# Qwiic_Adaptive_Switch_Input.net
KiCad netlist of a schematic drawn in EAGLE
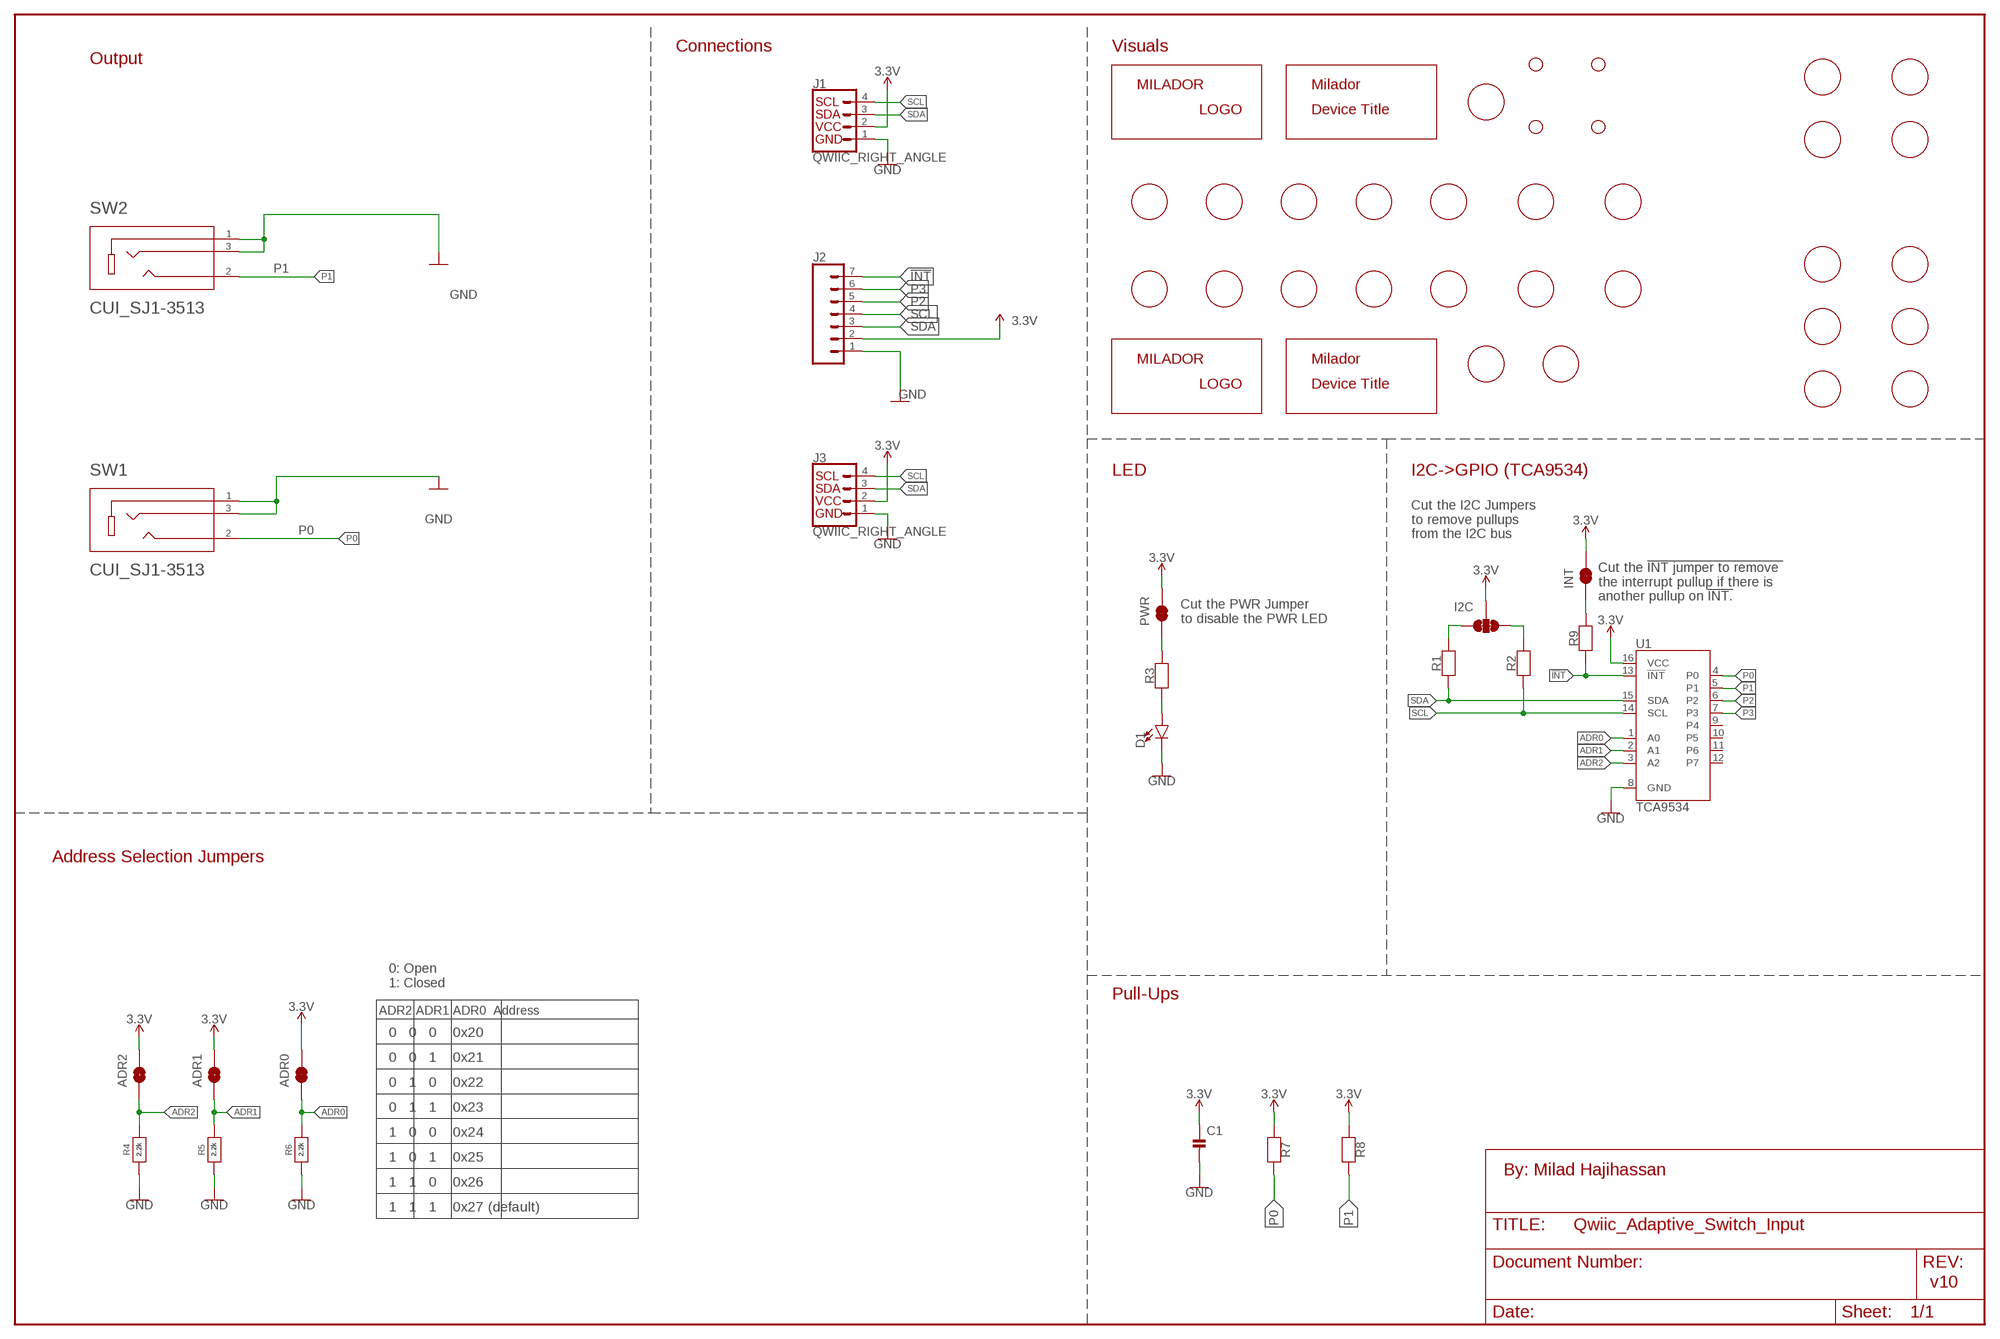
[diagram p0: schematic, sheet 1]

(export (version "E")
  (design (tool "Eeschema 10.0.6"))
  (components
    (comp (ref "ADR0")
      (value "JUMPERS-SMT_2_NC_TRACE_SILK")
      (footprint "eagle-import:JUMPERS_SMT-JUMPER_2_NC_TRACE_SILK")
      (libsource (lib "eagle-import") (part "JUMPERS-SMT_2_NC_TRACE_SILK"))
    )
    (comp (ref "ADR1")
      (value "JUMPERS-SMT_2_NC_TRACE_SILK")
      (footprint "eagle-import:JUMPERS_SMT-JUMPER_2_NC_TRACE_SILK")
      (libsource (lib "eagle-import") (part "JUMPERS-SMT_2_NC_TRACE_SILK"))
    )
    (comp (ref "ADR2")
      (value "JUMPERS-SMT_2_NC_TRACE_SILK")
      (footprint "eagle-import:JUMPERS_SMT-JUMPER_2_NC_TRACE_SILK")
      (libsource (lib "eagle-import") (part "JUMPERS-SMT_2_NC_TRACE_SILK"))
    )
    (comp (ref "C1")
      (value "0.1uF")
      (footprint "eagle-import:0805-MP")
      (libsource (lib "eagle-import") (part "CAP_CERAMIC-0805-MP"))
    )
    (comp (ref "D1")
      (value "RED")
      (footprint "eagle-import:CHIPLED_0805_NOOUTLINE")
      (libsource (lib "eagle-import") (part "LED0805_NOOUTLINE"))
    )
    (comp (ref "H1")
      (value "STAND-OFF-3.3")
      (footprint "eagle-import:STAND-OFF-3.3")
      (libsource (lib "eagle-import") (part "STAND-OFF-3.3"))
    )
    (comp (ref "H2")
      (value "STAND-OFF-3.3")
      (footprint "eagle-import:STAND-OFF-3.3")
      (libsource (lib "eagle-import") (part "STAND-OFF-3.3"))
    )
    (comp (ref "H3")
      (value "STAND-OFF-3.3")
      (footprint "eagle-import:STAND-OFF-3.3")
      (libsource (lib "eagle-import") (part "STAND-OFF-3.3"))
    )
    (comp (ref "H4")
      (value "STAND-OFF-3.3")
      (footprint "eagle-import:STAND-OFF-3.3")
      (libsource (lib "eagle-import") (part "STAND-OFF-3.3"))
    )
    (comp (ref "I2C")
      (value "JUMPERS_JUMPER-SMT_3_2-NC_TRACE_SILK")
      (footprint "eagle-import:JUMPERS_SMT-JUMPER_3_2-NC_TRACE_SILK")
      (libsource (lib "eagle-import") (part "JUMPERS_JUMPER-SMT_3_2-NC_TRACE_SILK"))
    )
    (comp (ref "INT")
      (value "JUMPERS-SMT_2_NC_TRACE_SILK")
      (footprint "eagle-import:JUMPERS_SMT-JUMPER_2_NC_TRACE_SILK")
      (libsource (lib "eagle-import") (part "JUMPERS-SMT_2_NC_TRACE_SILK"))
    )
    (comp (ref "J1")
      (value "QWIIC_RIGHT_ANGLE")
      (footprint "eagle-import:CONNECTORS_JST04_1MM_RA")
      (fields (field (name "PROD_ID") "CONN-13694"))
      (libsource (lib "eagle-import") (part "QWIIC_CONNECTORSJS-1MM"))
    )
    (comp (ref "J2")
      (value "CONNECTORS_CONN_071X07_NO_SILK")
      (footprint "eagle-import:CONNECTORS_1X07_NO_SILK")
      (libsource (lib "eagle-import") (part "CONNECTORS_CONN_071X07_NO_SILK"))
    )
    (comp (ref "J3")
      (value "QWIIC_RIGHT_ANGLE")
      (footprint "eagle-import:CONNECTORS_JST04_1MM_RA")
      (fields (field (name "PROD_ID") "CONN-13694"))
      (libsource (lib "eagle-import") (part "QWIIC_CONNECTORSJS-1MM"))
    )
    (comp (ref "LABEL_!INT_BOTTOM")
      (value "MILADOR-LABEL-!INT")
      (footprint "eagle-import:LABEL-!INT")
      (libsource (lib "eagle-import") (part "MILADOR-LABEL-!INT"))
    )
    (comp (ref "LABEL_!INT_TOP")
      (value "MILADOR-LABEL-!INT")
      (footprint "eagle-import:LABEL-!INT")
      (libsource (lib "eagle-import") (part "MILADOR-LABEL-!INT"))
    )
    (comp (ref "LABEL_3V_BOTTOM")
      (value "MILADOR-LABEL-3V")
      (footprint "eagle-import:LABEL-3V")
      (libsource (lib "eagle-import") (part "MILADOR-LABEL-3V"))
    )
    (comp (ref "LABEL_3V_TOP")
      (value "MILADOR-LABEL-3V")
      (footprint "eagle-import:LABEL-3V")
      (libsource (lib "eagle-import") (part "MILADOR-LABEL-3V"))
    )
    (comp (ref "LABEL_ADR0")
      (value "MILADOR-LABEL-ADR0")
      (footprint "eagle-import:LABEL-ADR0")
      (libsource (lib "eagle-import") (part "MILADOR-LABEL-ADR0"))
    )
    (comp (ref "LABEL_ADR1")
      (value "MILADOR-LABEL-ADR1")
      (footprint "eagle-import:LABEL-ADR1")
      (libsource (lib "eagle-import") (part "MILADOR-LABEL-ADR1"))
    )
    (comp (ref "LABEL_ADR2")
      (value "MILADOR-LABEL-ADR2")
      (footprint "eagle-import:LABEL-ADR2")
      (libsource (lib "eagle-import") (part "MILADOR-LABEL-ADR2"))
    )
    (comp (ref "LABEL_GND_BOTTOM")
      (value "MILADOR-LABEL-GND")
      (footprint "eagle-import:LABEL-GND")
      (libsource (lib "eagle-import") (part "MILADOR-LABEL-GND"))
    )
    (comp (ref "LABEL_GND_TOP")
      (value "MILADOR-LABEL-GND")
      (footprint "eagle-import:LABEL-GND")
      (libsource (lib "eagle-import") (part "MILADOR-LABEL-GND"))
    )
    (comp (ref "LABEL_I2C")
      (value "MILADOR-LABEL-I2C")
      (footprint "eagle-import:LABEL-I2C")
      (libsource (lib "eagle-import") (part "MILADOR-LABEL-I2C"))
    )
    (comp (ref "LABEL_I2C_ADDRESS")
      (value "MILADOR-LABEL-ADDRESS-0X27")
      (footprint "eagle-import:LABEL-ADDRESS-27")
      (libsource (lib "eagle-import") (part "MILADOR-LABEL-ADDRESS-0X27"))
    )
    (comp (ref "LABEL_INPUT_BOTTOM")
      (value "MILADOR-SWITCH-NAME-SW-INPUT")
      (footprint "eagle-import:SWITCH-INPUT")
      (libsource (lib "eagle-import") (part "MILADOR-SWITCH-NAME-SW-INPUT"))
    )
    (comp (ref "LABEL_INPUT_TOP")
      (value "MILADOR-SWITCH-NAME-SW-INPUT")
      (footprint "eagle-import:SWITCH-INPUT")
      (libsource (lib "eagle-import") (part "MILADOR-SWITCH-NAME-SW-INPUT"))
    )
    (comp (ref "LABEL_INT")
      (value "MILADOR-LABEL-INT")
      (footprint "eagle-import:LABEL-INT")
      (libsource (lib "eagle-import") (part "MILADOR-LABEL-INT"))
    )
    (comp (ref "LABEL_MILADOR_BOTTOM")
      (value "MILADOR-LOGO-")
      (footprint "eagle-import:MILADOR_LOGO1")
      (libsource (lib "eagle-import") (part "MILADOR-LOGO-"))
    )
    (comp (ref "LABEL_MILADOR_TOP")
      (value "MILADOR-LOGO-")
      (footprint "eagle-import:MILADOR_LOGO1")
      (libsource (lib "eagle-import") (part "MILADOR-LOGO-"))
    )
    (comp (ref "LABEL_P0_BOTTOM")
      (value "MILADOR-LABEL-P0")
      (footprint "eagle-import:LABEL-P0")
      (libsource (lib "eagle-import") (part "MILADOR-LABEL-P0"))
    )
    (comp (ref "LABEL_P1_BOTTOM")
      (value "MILADOR-LABEL-P1")
      (footprint "eagle-import:LABEL-P1")
      (libsource (lib "eagle-import") (part "MILADOR-LABEL-P1"))
    )
    (comp (ref "LABEL_P2_BOTTOM")
      (value "MILADOR-LABEL-P2")
      (footprint "eagle-import:LABEL-P2")
      (libsource (lib "eagle-import") (part "MILADOR-LABEL-P2"))
    )
    (comp (ref "LABEL_P2_TOP")
      (value "MILADOR-LABEL-P2")
      (footprint "eagle-import:LABEL-P2")
      (libsource (lib "eagle-import") (part "MILADOR-LABEL-P2"))
    )
    (comp (ref "LABEL_P3_BOTTOM")
      (value "MILADOR-LABEL-P3")
      (footprint "eagle-import:LABEL-P3")
      (libsource (lib "eagle-import") (part "MILADOR-LABEL-P3"))
    )
    (comp (ref "LABEL_P3_TOP")
      (value "MILADOR-LABEL-P3")
      (footprint "eagle-import:LABEL-P3")
      (libsource (lib "eagle-import") (part "MILADOR-LABEL-P3"))
    )
    (comp (ref "LABEL_PWR")
      (value "MILADOR-LABEL-PWR")
      (footprint "eagle-import:LABEL-PWR")
      (libsource (lib "eagle-import") (part "MILADOR-LABEL-PWR"))
    )
    (comp (ref "LABEL_SW1")
      (value "MILADOR-SWITCH-NAME-SW1")
      (footprint "eagle-import:SWITCH-SW1")
      (libsource (lib "eagle-import") (part "MILADOR-SWITCH-NAME-SW1"))
    )
    (comp (ref "LABEL_SW2")
      (value "MILADOR-SWITCH-NAME-SW2")
      (footprint "eagle-import:SWITCH-SW2")
      (libsource (lib "eagle-import") (part "MILADOR-SWITCH-NAME-SW2"))
    )
    (comp (ref "LABEL_TITLE_BOTTOM")
      (value "MILADOR-DEVICE-QWIIC-SWITCH")
      (footprint "eagle-import:MILADOR_QWIIC_SWITCH")
      (libsource (lib "eagle-import") (part "MILADOR-DEVICE-QWIIC-SWITCH"))
    )
    (comp (ref "LABEL_TITLE_TOP")
      (value "MILADOR-DEVICE-QWIIC-SWITCH-SM")
      (footprint "eagle-import:MILADOR_QWIIC_SWITCH_SM")
      (libsource (lib "eagle-import") (part "MILADOR-DEVICE-QWIIC-SWITCH-SM"))
    )
    (comp (ref "LABE_SCL_BOTTOM")
      (value "MILADOR-LABEL-SCL")
      (footprint "eagle-import:LABEL-SCL")
      (libsource (lib "eagle-import") (part "MILADOR-LABEL-SCL"))
    )
    (comp (ref "LABE_SCL_TOP")
      (value "MILADOR-LABEL-SCL")
      (footprint "eagle-import:LABEL-SCL")
      (libsource (lib "eagle-import") (part "MILADOR-LABEL-SCL"))
    )
    (comp (ref "LABE_SDA_BOTTOM")
      (value "MILADOR-LABEL-SDA")
      (footprint "eagle-import:LABEL-SDA")
      (libsource (lib "eagle-import") (part "MILADOR-LABEL-SDA"))
    )
    (comp (ref "LABE_SDA_TOP")
      (value "MILADOR-LABEL-SDA")
      (footprint "eagle-import:LABEL-SDA")
      (libsource (lib "eagle-import") (part "MILADOR-LABEL-SDA"))
    )
    (comp (ref "PWR")
      (value "JUMPERS-SMT_2_NC_TRACE_SILK")
      (footprint "eagle-import:JUMPERS_SMT-JUMPER_2_NC_TRACE_SILK")
      (libsource (lib "eagle-import") (part "JUMPERS-SMT_2_NC_TRACE_SILK"))
    )
    (comp (ref "R1")
      (value "2.2k")
      (footprint "eagle-import:0805-MP")
      (libsource (lib "eagle-import") (part "RESISTOR-0805-MP"))
    )
    (comp (ref "R2")
      (value "2.2k")
      (footprint "eagle-import:0805-MP")
      (libsource (lib "eagle-import") (part "RESISTOR-0805-MP"))
    )
    (comp (ref "R3")
      (value "1k")
      (footprint "eagle-import:0805-MP")
      (libsource (lib "eagle-import") (part "RESISTOR-0805-MP"))
    )
    (comp (ref "R4")
      (value "2.2k")
      (footprint "eagle-import:0805-MP")
      (libsource (lib "eagle-import") (part "RESISTOR-0805-MP"))
    )
    (comp (ref "R5")
      (value "2.2k")
      (footprint "eagle-import:0805-MP")
      (libsource (lib "eagle-import") (part "RESISTOR-0805-MP"))
    )
    (comp (ref "R6")
      (value "2.2k")
      (footprint "eagle-import:0805-MP")
      (libsource (lib "eagle-import") (part "RESISTOR-0805-MP"))
    )
    (comp (ref "R7")
      (value "4.7K")
      (footprint "eagle-import:0805-MP")
      (libsource (lib "eagle-import") (part "RESISTOR-0805-MP"))
    )
    (comp (ref "R8")
      (value "4.7K")
      (footprint "eagle-import:0805-MP")
      (libsource (lib "eagle-import") (part "RESISTOR-0805-MP"))
    )
    (comp (ref "R9")
      (value "10k")
      (footprint "eagle-import:0805-MP")
      (libsource (lib "eagle-import") (part "RESISTOR-0805-MP"))
    )
    (comp (ref "SW1")
      (value "CUI_SJ1-3513")
      (footprint "eagle-import:CUI_SJ1-3513")
      (libsource (lib "eagle-import") (part "CUI_SJ1-3513"))
    )
    (comp (ref "SW2")
      (value "CUI_SJ1-3513")
      (footprint "eagle-import:CUI_SJ1-3513")
      (libsource (lib "eagle-import") (part "CUI_SJ1-3513"))
    )
    (comp (ref "U1")
      (value "TCA9534")
      (footprint "eagle-import:16SOIC")
      (libsource (lib "eagle-import") (part "TCA9534DWR"))
    )
  )
  (nets
    (net (code "1") (name "/~{INT}") (class "Default")
      (node (ref "J2") (pin "7") (pinfunction "7_7") (pintype "passive"))
      (node (ref "R9") (pin "1") (pinfunction "1_1") (pintype "passive"))
      (node (ref "U1") (pin "13") (pinfunction "~{INT}_13") (pintype "bidirectional"))
    )
    (net (code "2") (name "3.3V") (class "Default")
      (node (ref "ADR0") (pin "2") (pinfunction "2_2") (pintype "passive"))
      (node (ref "ADR1") (pin "2") (pinfunction "2_2") (pintype "passive"))
      (node (ref "ADR2") (pin "2") (pinfunction "2_2") (pintype "passive"))
      (node (ref "C1") (pin "1") (pinfunction "1_1") (pintype "passive"))
      (node (ref "I2C") (pin "2") (pinfunction "2_2") (pintype "passive"))
      (node (ref "INT") (pin "2") (pinfunction "2_2") (pintype "passive"))
      (node (ref "J1") (pin "2") (pinfunction "2_2") (pintype "power_in"))
      (node (ref "J2") (pin "2") (pinfunction "2_2") (pintype "passive"))
      (node (ref "J3") (pin "2") (pinfunction "2_2") (pintype "power_in"))
      (node (ref "PWR") (pin "2") (pinfunction "2_2") (pintype "passive"))
      (node (ref "R7") (pin "1") (pinfunction "1_1") (pintype "passive"))
      (node (ref "R8") (pin "1") (pinfunction "1_1") (pintype "passive"))
      (node (ref "U1") (pin "16") (pinfunction "VCC_16") (pintype "bidirectional"))
    )
    (net (code "3") (name "ADR0") (class "Default")
      (node (ref "ADR0") (pin "1") (pinfunction "1_1") (pintype "passive"))
      (node (ref "R6") (pin "2") (pinfunction "2_2") (pintype "passive"))
      (node (ref "U1") (pin "1") (pinfunction "A0_1") (pintype "bidirectional"))
    )
    (net (code "4") (name "ADR1") (class "Default")
      (node (ref "ADR1") (pin "1") (pinfunction "1_1") (pintype "passive"))
      (node (ref "R5") (pin "2") (pinfunction "2_2") (pintype "passive"))
      (node (ref "U1") (pin "2") (pinfunction "A1_2") (pintype "bidirectional"))
    )
    (net (code "5") (name "ADR2") (class "Default")
      (node (ref "ADR2") (pin "1") (pinfunction "1_1") (pintype "passive"))
      (node (ref "R4") (pin "2") (pinfunction "2_2") (pintype "passive"))
      (node (ref "U1") (pin "3") (pinfunction "A2_3") (pintype "bidirectional"))
    )
    (net (code "6") (name "GND") (class "Default")
      (node (ref "C1") (pin "2") (pinfunction "2_2") (pintype "passive"))
      (node (ref "D1") (pin "C") (pinfunction "C_C") (pintype "passive"))
      (node (ref "J1") (pin "1") (pinfunction "1_1") (pintype "power_in"))
      (node (ref "J2") (pin "1") (pinfunction "1_1") (pintype "passive"))
      (node (ref "J3") (pin "1") (pinfunction "1_1") (pintype "power_in"))
      (node (ref "R4") (pin "1") (pinfunction "1_1") (pintype "passive"))
      (node (ref "R5") (pin "1") (pinfunction "1_1") (pintype "passive"))
      (node (ref "R6") (pin "1") (pinfunction "1_1") (pintype "passive"))
      (node (ref "SW1") (pin "1") (pinfunction "1_1") (pintype "passive"))
      (node (ref "SW1") (pin "3") (pinfunction "3_3") (pintype "passive"))
      (node (ref "SW2") (pin "1") (pinfunction "1_1") (pintype "passive"))
      (node (ref "SW2") (pin "3") (pinfunction "3_3") (pintype "passive"))
      (node (ref "U1") (pin "8") (pinfunction "GND_8") (pintype "bidirectional"))
    )
    (net (code "7") (name "Net-(D1-PadA)") (class "Default")
      (node (ref "D1") (pin "A") (pinfunction "A_A") (pintype "passive"))
      (node (ref "R3") (pin "1") (pinfunction "1_1") (pintype "passive"))
    )
    (net (code "8") (name "Net-(I2C-Pad1)") (class "Default")
      (node (ref "I2C") (pin "1") (pinfunction "1_1") (pintype "passive"))
      (node (ref "R1") (pin "2") (pinfunction "2_2") (pintype "passive"))
    )
    (net (code "9") (name "Net-(I2C-Pad3)") (class "Default")
      (node (ref "I2C") (pin "3") (pinfunction "3_3") (pintype "passive"))
      (node (ref "R2") (pin "2") (pinfunction "2_2") (pintype "passive"))
    )
    (net (code "10") (name "Net-(INT-Pad1)") (class "Default")
      (node (ref "INT") (pin "1") (pinfunction "1_1") (pintype "passive"))
      (node (ref "R9") (pin "2") (pinfunction "2_2") (pintype "passive"))
    )
    (net (code "11") (name "Net-(PWR-Pad1)") (class "Default")
      (node (ref "PWR") (pin "1") (pinfunction "1_1") (pintype "passive"))
      (node (ref "R3") (pin "2") (pinfunction "2_2") (pintype "passive"))
    )
    (net (code "12") (name "P0") (class "Default")
      (node (ref "R7") (pin "2") (pinfunction "2_2") (pintype "passive"))
      (node (ref "SW1") (pin "2") (pinfunction "2_2") (pintype "passive"))
      (node (ref "U1") (pin "4") (pinfunction "P0_4") (pintype "bidirectional"))
    )
    (net (code "13") (name "P1") (class "Default")
      (node (ref "R8") (pin "2") (pinfunction "2_2") (pintype "passive"))
      (node (ref "SW2") (pin "2") (pinfunction "2_2") (pintype "passive"))
      (node (ref "U1") (pin "5") (pinfunction "P1_5") (pintype "bidirectional"))
    )
    (net (code "14") (name "P2") (class "Default")
      (node (ref "J2") (pin "5") (pinfunction "5_5") (pintype "passive"))
      (node (ref "U1") (pin "6") (pinfunction "P2_6") (pintype "bidirectional"))
    )
    (net (code "15") (name "P3") (class "Default")
      (node (ref "J2") (pin "6") (pinfunction "6_6") (pintype "passive"))
      (node (ref "U1") (pin "7") (pinfunction "P3_7") (pintype "bidirectional"))
    )
    (net (code "16") (name "SCL") (class "Default")
      (node (ref "J1") (pin "4") (pinfunction "4_4") (pintype "passive"))
      (node (ref "J2") (pin "4") (pinfunction "4_4") (pintype "passive"))
      (node (ref "J3") (pin "4") (pinfunction "4_4") (pintype "passive"))
      (node (ref "R2") (pin "1") (pinfunction "1_1") (pintype "passive"))
      (node (ref "U1") (pin "14") (pinfunction "SCL_14") (pintype "bidirectional"))
    )
    (net (code "17") (name "SDA") (class "Default")
      (node (ref "J1") (pin "3") (pinfunction "3_3") (pintype "passive"))
      (node (ref "J2") (pin "3") (pinfunction "3_3") (pintype "passive"))
      (node (ref "J3") (pin "3") (pinfunction "3_3") (pintype "passive"))
      (node (ref "R1") (pin "1") (pinfunction "1_1") (pintype "passive"))
      (node (ref "U1") (pin "15") (pinfunction "SDA_15") (pintype "bidirectional"))
    )
    (net (code "18") (name "unconnected-(U1-P4-Pad9)") (class "Default")
      (node (ref "U1") (pin "9") (pinfunction "P4_9") (pintype "bidirectional"))
    )
    (net (code "19") (name "unconnected-(U1-P5-Pad10)") (class "Default")
      (node (ref "U1") (pin "10") (pinfunction "P5_10") (pintype "bidirectional"))
    )
    (net (code "20") (name "unconnected-(U1-P6-Pad11)") (class "Default")
      (node (ref "U1") (pin "11") (pinfunction "P6_11") (pintype "bidirectional"))
    )
    (net (code "21") (name "unconnected-(U1-P7-Pad12)") (class "Default")
      (node (ref "U1") (pin "12") (pinfunction "P7_12") (pintype "bidirectional"))
    )
  )
)
